# led.net
KiCad netlist of a schematic drawn in Altium Designer
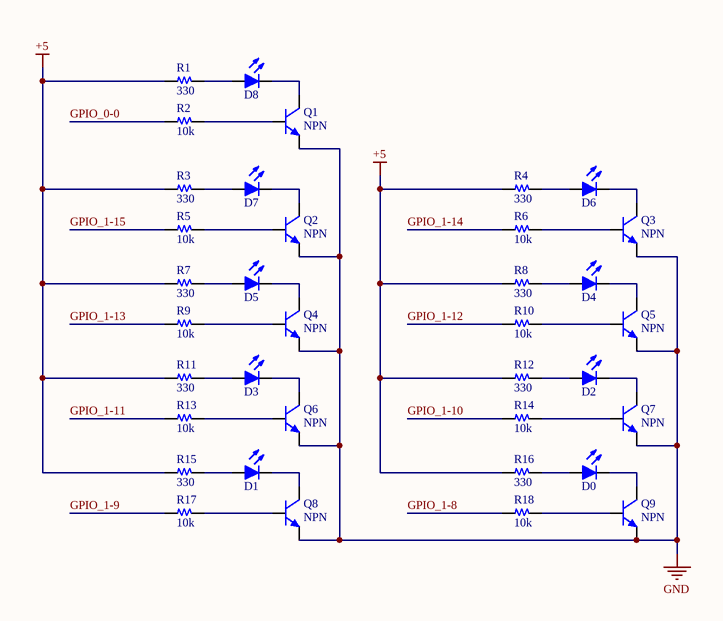
[diagram p0: led.SchDoc]

(export (version "E")
  (design (tool "Eeschema 10.0.6"))
  (components
    (comp (ref "D0")
      (value "Led")
      (footprint "Led 0805")
      (description "Typical LED")
      (libsource (lib "chipfc_libs") (part "Led"))
    )
    (comp (ref "D1")
      (value "Led")
      (footprint "Led 0805")
      (description "Typical LED")
      (libsource (lib "chipfc_libs") (part "Led"))
    )
    (comp (ref "D2")
      (value "Led")
      (footprint "Led 0805")
      (description "Typical LED")
      (libsource (lib "chipfc_libs") (part "Led"))
    )
    (comp (ref "D3")
      (value "Led")
      (footprint "Led 0805")
      (description "Typical LED")
      (libsource (lib "chipfc_libs") (part "Led"))
    )
    (comp (ref "D4")
      (value "Led")
      (footprint "Led 0805")
      (description "Typical LED")
      (libsource (lib "chipfc_libs") (part "Led"))
    )
    (comp (ref "D5")
      (value "Led")
      (footprint "Led 0805")
      (description "Typical LED")
      (libsource (lib "chipfc_libs") (part "Led"))
    )
    (comp (ref "D6")
      (value "Led")
      (footprint "Led 0805")
      (description "Typical LED")
      (libsource (lib "chipfc_libs") (part "Led"))
    )
    (comp (ref "D7")
      (value "Led")
      (footprint "Led 0805")
      (description "Typical LED")
      (libsource (lib "chipfc_libs") (part "Led"))
    )
    (comp (ref "D8")
      (value "Led")
      (footprint "Led 0805 RED")
      (description "Typical LED")
      (libsource (lib "chipfc_libs") (part "Led"))
    )
    (comp (ref "Q1")
      (value "NPN")
      (footprint "SOT-23")
      (description "NPN Bipolar Transistor")
      (libsource (lib "chipfc_libs") (part "Transistor NPN"))
    )
    (comp (ref "Q2")
      (value "NPN")
      (footprint "SOT-23")
      (description "NPN Bipolar Transistor")
      (libsource (lib "chipfc_libs") (part "Transistor NPN"))
    )
    (comp (ref "Q3")
      (value "NPN")
      (footprint "SOT-23")
      (description "NPN Bipolar Transistor")
      (libsource (lib "chipfc_libs") (part "Transistor NPN"))
    )
    (comp (ref "Q4")
      (value "NPN")
      (footprint "SOT-23")
      (description "NPN Bipolar Transistor")
      (libsource (lib "chipfc_libs") (part "Transistor NPN"))
    )
    (comp (ref "Q5")
      (value "NPN")
      (footprint "SOT-23")
      (description "NPN Bipolar Transistor")
      (libsource (lib "chipfc_libs") (part "Transistor NPN"))
    )
    (comp (ref "Q6")
      (value "NPN")
      (footprint "SOT-23")
      (description "NPN Bipolar Transistor")
      (libsource (lib "chipfc_libs") (part "Transistor NPN"))
    )
    (comp (ref "Q7")
      (value "NPN")
      (footprint "SOT-23")
      (description "NPN Bipolar Transistor")
      (libsource (lib "chipfc_libs") (part "Transistor NPN"))
    )
    (comp (ref "Q8")
      (value "NPN")
      (footprint "SOT-23")
      (description "NPN Bipolar Transistor")
      (libsource (lib "chipfc_libs") (part "Transistor NPN"))
    )
    (comp (ref "Q9")
      (value "NPN")
      (footprint "SOT-23")
      (description "NPN Bipolar Transistor")
      (libsource (lib "chipfc_libs") (part "Transistor NPN"))
    )
    (comp (ref "R1")
      (value "330")
      (footprint "R 0603")
      (description "Resistor")
      (libsource (lib "chipfc_libs") (part "Resistor"))
    )
    (comp (ref "R2")
      (value "10k")
      (footprint "R 0603")
      (description "Resistor")
      (libsource (lib "chipfc_libs") (part "Resistor"))
    )
    (comp (ref "R3")
      (value "330")
      (footprint "R 0603")
      (description "Resistor")
      (libsource (lib "chipfc_libs") (part "Resistor"))
    )
    (comp (ref "R4")
      (value "330")
      (footprint "R 0603")
      (description "Resistor")
      (libsource (lib "chipfc_libs") (part "Resistor"))
    )
    (comp (ref "R5")
      (value "10k")
      (footprint "R 0603")
      (description "Resistor")
      (libsource (lib "chipfc_libs") (part "Resistor"))
    )
    (comp (ref "R6")
      (value "10k")
      (footprint "R 0603")
      (description "Resistor")
      (libsource (lib "chipfc_libs") (part "Resistor"))
    )
    (comp (ref "R7")
      (value "330")
      (footprint "R 0603")
      (description "Resistor")
      (libsource (lib "chipfc_libs") (part "Resistor"))
    )
    (comp (ref "R8")
      (value "330")
      (footprint "R 0603")
      (description "Resistor")
      (libsource (lib "chipfc_libs") (part "Resistor"))
    )
    (comp (ref "R9")
      (value "10k")
      (footprint "R 0603")
      (description "Resistor")
      (libsource (lib "chipfc_libs") (part "Resistor"))
    )
    (comp (ref "R10")
      (value "10k")
      (footprint "R 0603")
      (description "Resistor")
      (libsource (lib "chipfc_libs") (part "Resistor"))
    )
    (comp (ref "R11")
      (value "330")
      (footprint "R 0603")
      (description "Resistor")
      (libsource (lib "chipfc_libs") (part "Resistor"))
    )
    (comp (ref "R12")
      (value "330")
      (footprint "R 0603")
      (description "Resistor")
      (libsource (lib "chipfc_libs") (part "Resistor"))
    )
    (comp (ref "R13")
      (value "10k")
      (footprint "R 0603")
      (description "Resistor")
      (libsource (lib "chipfc_libs") (part "Resistor"))
    )
    (comp (ref "R14")
      (value "10k")
      (footprint "R 0603")
      (description "Resistor")
      (libsource (lib "chipfc_libs") (part "Resistor"))
    )
    (comp (ref "R15")
      (value "330")
      (footprint "R 0603")
      (description "Resistor")
      (libsource (lib "chipfc_libs") (part "Resistor"))
    )
    (comp (ref "R16")
      (value "330")
      (footprint "R 0603")
      (description "Resistor")
      (libsource (lib "chipfc_libs") (part "Resistor"))
    )
    (comp (ref "R17")
      (value "10k")
      (footprint "R 0603")
      (description "Resistor")
      (libsource (lib "chipfc_libs") (part "Resistor"))
    )
    (comp (ref "R18")
      (value "10k")
      (footprint "R 0603")
      (description "Resistor")
      (libsource (lib "chipfc_libs") (part "Resistor"))
    )
  )
  (nets
    (net (code "1") (name "+5") (class "Default")
      (node (ref "R1") (pin "1") (pinfunction "1_1") (pintype "passive"))
      (node (ref "R11") (pin "1") (pinfunction "1_1") (pintype "passive"))
      (node (ref "R12") (pin "1") (pinfunction "1_1") (pintype "passive"))
      (node (ref "R15") (pin "1") (pinfunction "1_1") (pintype "passive"))
      (node (ref "R16") (pin "1") (pinfunction "1_1") (pintype "passive"))
      (node (ref "R3") (pin "1") (pinfunction "1_1") (pintype "passive"))
      (node (ref "R4") (pin "1") (pinfunction "1_1") (pintype "passive"))
      (node (ref "R7") (pin "1") (pinfunction "1_1") (pintype "passive"))
      (node (ref "R8") (pin "1") (pinfunction "1_1") (pintype "passive"))
    )
    (net (code "2") (name "/GPIO_0-0") (class "Default")
      (node (ref "R2") (pin "1") (pinfunction "1_1") (pintype "passive"))
    )
    (net (code "3") (name "/GPIO_1-8") (class "Default")
      (node (ref "R18") (pin "1") (pinfunction "1_1") (pintype "passive"))
    )
    (net (code "4") (name "/GPIO_1-9") (class "Default")
      (node (ref "R17") (pin "1") (pinfunction "1_1") (pintype "passive"))
    )
    (net (code "5") (name "/GPIO_1-10") (class "Default")
      (node (ref "R14") (pin "1") (pinfunction "1_1") (pintype "passive"))
    )
    (net (code "6") (name "/GPIO_1-11") (class "Default")
      (node (ref "R13") (pin "1") (pinfunction "1_1") (pintype "passive"))
    )
    (net (code "7") (name "/GPIO_1-12") (class "Default")
      (node (ref "R10") (pin "1") (pinfunction "1_1") (pintype "passive"))
    )
    (net (code "8") (name "/GPIO_1-13") (class "Default")
      (node (ref "R9") (pin "1") (pinfunction "1_1") (pintype "passive"))
    )
    (net (code "9") (name "/GPIO_1-14") (class "Default")
      (node (ref "R6") (pin "1") (pinfunction "1_1") (pintype "passive"))
    )
    (net (code "10") (name "/GPIO_1-15") (class "Default")
      (node (ref "R5") (pin "1") (pinfunction "1_1") (pintype "passive"))
    )
    (net (code "11") (name "GND") (class "Default")
      (node (ref "Q1") (pin "2") (pinfunction "E_2") (pintype "passive"))
      (node (ref "Q2") (pin "2") (pinfunction "E_2") (pintype "passive"))
      (node (ref "Q3") (pin "2") (pinfunction "E_2") (pintype "passive"))
      (node (ref "Q4") (pin "2") (pinfunction "E_2") (pintype "passive"))
      (node (ref "Q5") (pin "2") (pinfunction "E_2") (pintype "passive"))
      (node (ref "Q6") (pin "2") (pinfunction "E_2") (pintype "passive"))
      (node (ref "Q7") (pin "2") (pinfunction "E_2") (pintype "passive"))
      (node (ref "Q8") (pin "2") (pinfunction "E_2") (pintype "passive"))
      (node (ref "Q9") (pin "2") (pinfunction "E_2") (pintype "passive"))
    )
    (net (code "12") (name "Net-(D0-A)") (class "Default")
      (node (ref "D0") (pin "1") (pinfunction "A_1") (pintype "passive"))
      (node (ref "R16") (pin "2") (pinfunction "2_2") (pintype "passive"))
    )
    (net (code "13") (name "Net-(D0-K)") (class "Default")
      (node (ref "D0") (pin "2") (pinfunction "K_2") (pintype "passive"))
      (node (ref "Q9") (pin "3") (pinfunction "C_3") (pintype "passive"))
    )
    (net (code "14") (name "Net-(D1-A)") (class "Default")
      (node (ref "D1") (pin "1") (pinfunction "A_1") (pintype "passive"))
      (node (ref "R15") (pin "2") (pinfunction "2_2") (pintype "passive"))
    )
    (net (code "15") (name "Net-(D1-K)") (class "Default")
      (node (ref "D1") (pin "2") (pinfunction "K_2") (pintype "passive"))
      (node (ref "Q8") (pin "3") (pinfunction "C_3") (pintype "passive"))
    )
    (net (code "16") (name "Net-(D2-A)") (class "Default")
      (node (ref "D2") (pin "1") (pinfunction "A_1") (pintype "passive"))
      (node (ref "R12") (pin "2") (pinfunction "2_2") (pintype "passive"))
    )
    (net (code "17") (name "Net-(D2-K)") (class "Default")
      (node (ref "D2") (pin "2") (pinfunction "K_2") (pintype "passive"))
      (node (ref "Q7") (pin "3") (pinfunction "C_3") (pintype "passive"))
    )
    (net (code "18") (name "Net-(D3-A)") (class "Default")
      (node (ref "D3") (pin "1") (pinfunction "A_1") (pintype "passive"))
      (node (ref "R11") (pin "2") (pinfunction "2_2") (pintype "passive"))
    )
    (net (code "19") (name "Net-(D3-K)") (class "Default")
      (node (ref "D3") (pin "2") (pinfunction "K_2") (pintype "passive"))
      (node (ref "Q6") (pin "3") (pinfunction "C_3") (pintype "passive"))
    )
    (net (code "20") (name "Net-(D4-A)") (class "Default")
      (node (ref "D4") (pin "1") (pinfunction "A_1") (pintype "passive"))
      (node (ref "R8") (pin "2") (pinfunction "2_2") (pintype "passive"))
    )
    (net (code "21") (name "Net-(D4-K)") (class "Default")
      (node (ref "D4") (pin "2") (pinfunction "K_2") (pintype "passive"))
      (node (ref "Q5") (pin "3") (pinfunction "C_3") (pintype "passive"))
    )
    (net (code "22") (name "Net-(D5-A)") (class "Default")
      (node (ref "D5") (pin "1") (pinfunction "A_1") (pintype "passive"))
      (node (ref "R7") (pin "2") (pinfunction "2_2") (pintype "passive"))
    )
    (net (code "23") (name "Net-(D5-K)") (class "Default")
      (node (ref "D5") (pin "2") (pinfunction "K_2") (pintype "passive"))
      (node (ref "Q4") (pin "3") (pinfunction "C_3") (pintype "passive"))
    )
    (net (code "24") (name "Net-(D6-A)") (class "Default")
      (node (ref "D6") (pin "1") (pinfunction "A_1") (pintype "passive"))
      (node (ref "R4") (pin "2") (pinfunction "2_2") (pintype "passive"))
    )
    (net (code "25") (name "Net-(D6-K)") (class "Default")
      (node (ref "D6") (pin "2") (pinfunction "K_2") (pintype "passive"))
      (node (ref "Q3") (pin "3") (pinfunction "C_3") (pintype "passive"))
    )
    (net (code "26") (name "Net-(D7-A)") (class "Default")
      (node (ref "D7") (pin "1") (pinfunction "A_1") (pintype "passive"))
      (node (ref "R3") (pin "2") (pinfunction "2_2") (pintype "passive"))
    )
    (net (code "27") (name "Net-(D7-K)") (class "Default")
      (node (ref "D7") (pin "2") (pinfunction "K_2") (pintype "passive"))
      (node (ref "Q2") (pin "3") (pinfunction "C_3") (pintype "passive"))
    )
    (net (code "28") (name "Net-(D8-A)") (class "Default")
      (node (ref "D8") (pin "1") (pinfunction "A_1") (pintype "passive"))
      (node (ref "R1") (pin "2") (pinfunction "2_2") (pintype "passive"))
    )
    (net (code "29") (name "Net-(D8-K)") (class "Default")
      (node (ref "D8") (pin "2") (pinfunction "K_2") (pintype "passive"))
      (node (ref "Q1") (pin "3") (pinfunction "C_3") (pintype "passive"))
    )
    (net (code "30") (name "Net-(Q1-B)") (class "Default")
      (node (ref "Q1") (pin "1") (pinfunction "B_1") (pintype "passive"))
      (node (ref "R2") (pin "2") (pinfunction "2_2") (pintype "passive"))
    )
    (net (code "31") (name "Net-(Q2-B)") (class "Default")
      (node (ref "Q2") (pin "1") (pinfunction "B_1") (pintype "passive"))
      (node (ref "R5") (pin "2") (pinfunction "2_2") (pintype "passive"))
    )
    (net (code "32") (name "Net-(Q3-B)") (class "Default")
      (node (ref "Q3") (pin "1") (pinfunction "B_1") (pintype "passive"))
      (node (ref "R6") (pin "2") (pinfunction "2_2") (pintype "passive"))
    )
    (net (code "33") (name "Net-(Q4-B)") (class "Default")
      (node (ref "Q4") (pin "1") (pinfunction "B_1") (pintype "passive"))
      (node (ref "R9") (pin "2") (pinfunction "2_2") (pintype "passive"))
    )
    (net (code "34") (name "Net-(Q5-B)") (class "Default")
      (node (ref "Q5") (pin "1") (pinfunction "B_1") (pintype "passive"))
      (node (ref "R10") (pin "2") (pinfunction "2_2") (pintype "passive"))
    )
    (net (code "35") (name "Net-(Q6-B)") (class "Default")
      (node (ref "Q6") (pin "1") (pinfunction "B_1") (pintype "passive"))
      (node (ref "R13") (pin "2") (pinfunction "2_2") (pintype "passive"))
    )
    (net (code "36") (name "Net-(Q7-B)") (class "Default")
      (node (ref "Q7") (pin "1") (pinfunction "B_1") (pintype "passive"))
      (node (ref "R14") (pin "2") (pinfunction "2_2") (pintype "passive"))
    )
    (net (code "37") (name "Net-(Q8-B)") (class "Default")
      (node (ref "Q8") (pin "1") (pinfunction "B_1") (pintype "passive"))
      (node (ref "R17") (pin "2") (pinfunction "2_2") (pintype "passive"))
    )
    (net (code "38") (name "Net-(Q9-B)") (class "Default")
      (node (ref "Q9") (pin "1") (pinfunction "B_1") (pintype "passive"))
      (node (ref "R18") (pin "2") (pinfunction "2_2") (pintype "passive"))
    )
  )
)
